# 07.net
KiCad netlist of a schematic drawn in Altium Designer
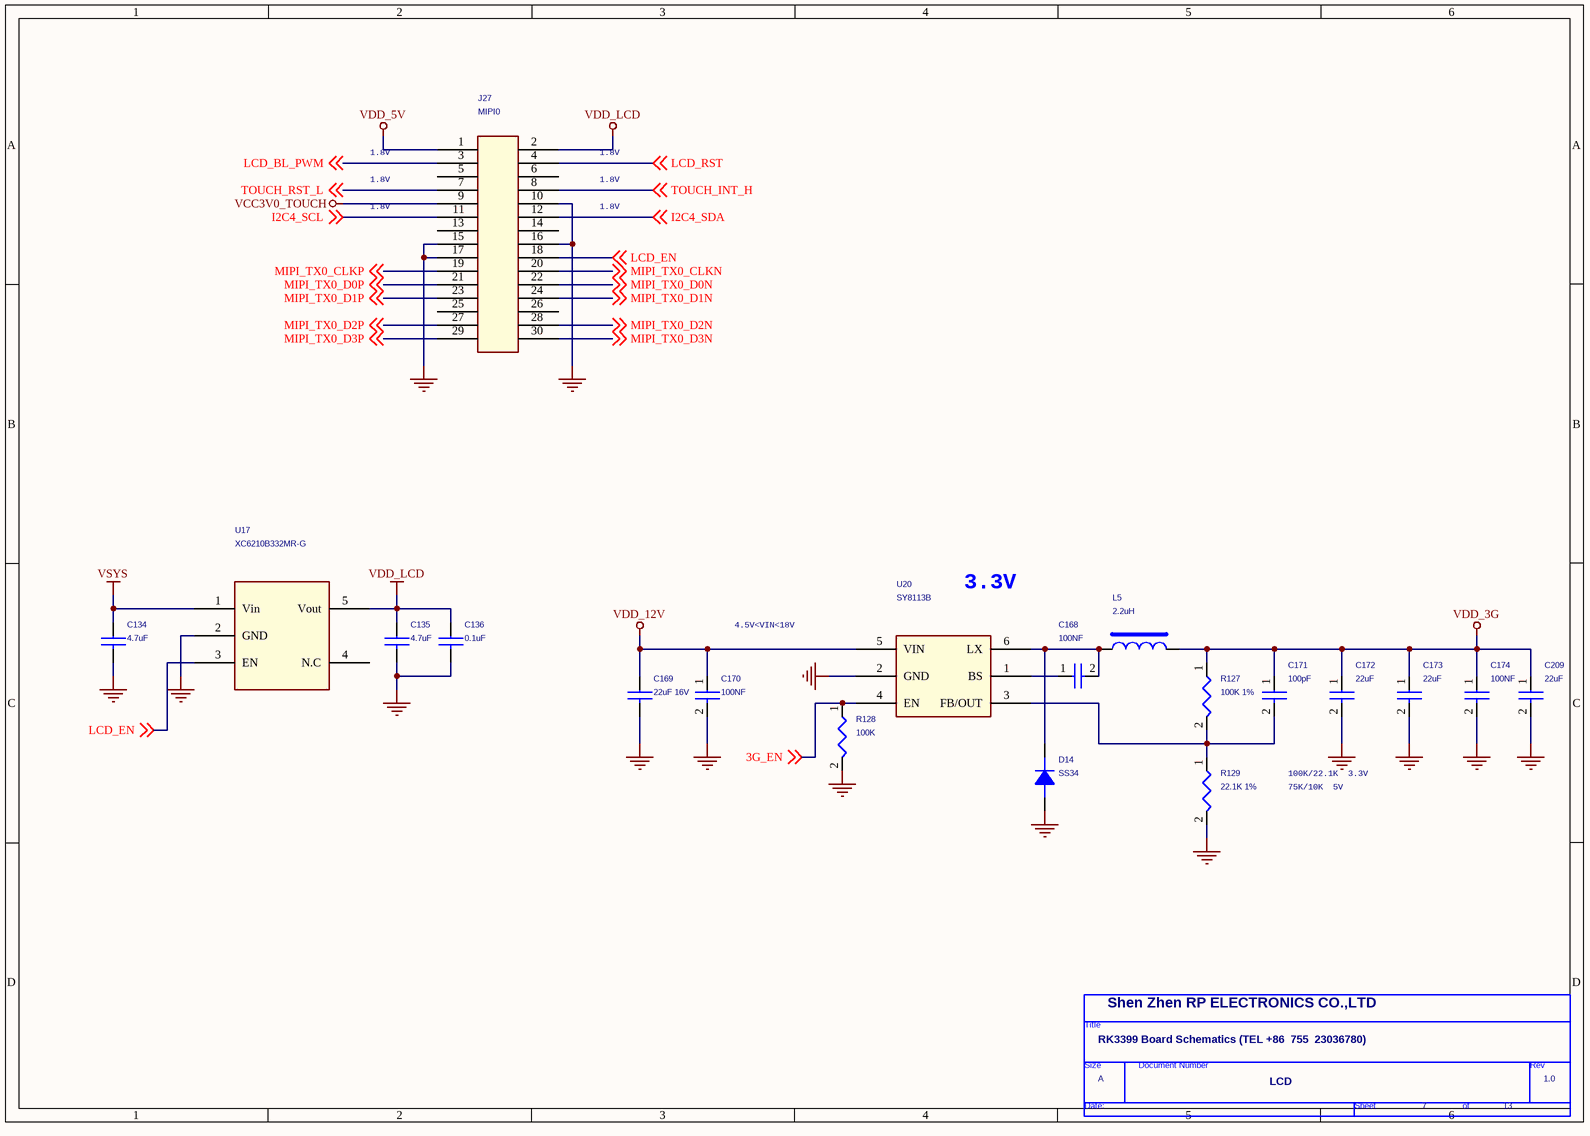
[diagram p0: 07.SchDoc]

(export (version "E")
  (design (tool "Eeschema 10.0.6"))
  (components
    (comp (ref "C134") (value "4.7uF") (libsource (lib "*") (part "CAP NP_Dup8")))
    (comp (ref "C135") (value "4.7uF") (libsource (lib "*") (part "CAP NP_Dup8")))
    (comp (ref "C136") (value "0.1uF") (libsource (lib "*") (part "CAP NP_Dup8")))
    (comp (ref "C168")
      (value "100NF")
      (description "cap,100.00nF,+/-10%,25V,X5R,C0402")
      (fields
        (field (name "VOLTAGE") "25V")
        (field (name "TOLERANCE") "10%")
        (field (name "CREATED BY") "JJJ")
      )
      (libsource (lib "*") (part "CAP NP_Dup2"))
    )
    (comp (ref "C169") (value "22uF 16V") (libsource (lib "*") (part "CAP NP_Dup8")))
    (comp (ref "C170")
      (value "100NF")
      (description "cap,100.00nF,+/-10%,25V,X5R,C0402")
      (fields
        (field (name "VOLTAGE") "25V")
        (field (name "MANUFACTURER") "TDK")
        (field (name "CREATED BY") "JJJ")
      )
      (libsource (lib "*") (part "CAP NP_Dup2"))
    )
    (comp (ref "C171")
      (value "100pF")
      (description "cap,100.00pF,+/-5%,50V,C0G,C0402")
      (fields
        (field (name "VOLTAGE") "50V")
        (field (name "MANUFACTURER") "TDK")
        (field (name "CREATED BY") "JJJ")
      )
      (libsource (lib "*") (part "CAP NP_Dup2"))
    )
    (comp (ref "C172")
      (value "22uF")
      (description "cap,22.00uF,+/-10%,10V,X5R,C0805")
      (fields
        (field (name "VOLTAGE") "10V")
        (field (name "MANUFACTURER") "TDK")
        (field (name "CREATED BY") "JJJ")
      )
      (libsource (lib "*") (part "CAP NP_Dup2"))
    )
    (comp (ref "C173")
      (value "22uF")
      (description "cap,10.00uF,+/-10%,10V,X5R,C0805")
      (fields
        (field (name "VOLTAGE") "10V")
        (field (name "MANUFACTURER") "TDK")
        (field (name "CREATED BY") "JJJ")
      )
      (libsource (lib "*") (part "CAP NP_Dup2"))
    )
    (comp (ref "C174")
      (value "100NF")
      (description "cap,100.00nF,+/-10%,16V,X5R,C0402")
      (fields
        (field (name "VOLTAGE") "16V")
        (field (name "MANUFACTURER") "TDK")
        (field (name "CREATED BY") "JJJ")
      )
      (libsource (lib "*") (part "CAP NP_Dup2"))
    )
    (comp (ref "C209")
      (value "22uF")
      (description "cap,22.00uF,+/-10%,10V,X5R,C0805")
      (fields
        (field (name "VOLTAGE") "10V")
        (field (name "MANUFACTURER") "TDK")
        (field (name "CREATED BY") "JJJ")
      )
      (libsource (lib "*") (part "CAP NP_Dup2"))
    )
    (comp (ref "D14") (value "SS34") (libsource (lib "*") (part "DIODE_Dup1")))
    (comp (ref "J27") (value "MIPI0") (libsource (lib "*") (part "CON20_5")))
    (comp (ref "L5")
      (value "2.2uH")
      (description "Power Inductor,3.3uH,0.2,IND_404030")
      (fields
        (field (name "MANUFACTURER") "sunlord")
        (field (name "TOLERANCE") "20%")
        (field (name "CREATED BY") "YTL")
      )
      (libsource (lib "*") (part "INDUCTORS OF FERRITE"))
    )
    (comp (ref "R127")
      (value "100K 1%")
      (footprint "0805")
      (description "通用厚膜电阻,75K,+/-1%,R0402,1/16W.")
      (fields
        (field (name "TOLERANCE") "1%")
        (field (name "MANUFACTURER") "YAGEO")
        (field (name "CREATED BY") "YTL")
      )
      (libsource (lib "*") (part "RESISTOR_Dup1"))
    )
    (comp (ref "R128")
      (value "100K")
      (footprint "0805")
      (description "通用厚膜电阻,10K,+/-1%,R0402,1/16W.")
      (fields
        (field (name "TOLERANCE") "1%")
        (field (name "MANUFACTURER") "YAGEO")
        (field (name "CREATED BY") "YTL")
      )
      (libsource (lib "*") (part "RESISTOR_Dup1"))
    )
    (comp (ref "R129")
      (value "22.1K 1%")
      (footprint "0805")
      (description "通用厚膜电阻,10K,+/-1%,R0402,1/16W.")
      (fields
        (field (name "TOLERANCE") "1%")
        (field (name "MANUFACTURER") "YAGEO")
        (field (name "CREATED BY") "YTL")
      )
      (libsource (lib "*") (part "RESISTOR_Dup1"))
    )
    (comp (ref "U17") (value "XC6210B332MR-G") (libsource (lib "*") (part "XC6219_2")))
    (comp (ref "U20")
      (value "SY8113B")
      (fields (field (name "MANUFACTURER") "Silergy（矽力杰）") (field (name "CREATED BY") "JJJ"))
      (libsource (lib "*") (part "DCDC_SY8113"))
    )
  )
  (nets
    (net (code "1") (name "3G_EN") (class "Default")
      (node (ref "R128") (pin "1") (pinfunction "1_1") (pintype "passive"))
      (node (ref "U20") (pin "4") (pinfunction "EN_4") (pintype "passive"))
    )
    (net (code "2") (name "GND") (class "Default")
      (node (ref "C134") (pin "2") (pinfunction "2_2") (pintype "passive"))
      (node (ref "C135") (pin "2") (pinfunction "2_2") (pintype "passive"))
      (node (ref "C136") (pin "2") (pinfunction "2_2") (pintype "passive"))
      (node (ref "C169") (pin "2") (pinfunction "2_2") (pintype "passive"))
      (node (ref "C170") (pin "2") (pinfunction "2_2") (pintype "passive"))
      (node (ref "C172") (pin "2") (pinfunction "2_2") (pintype "passive"))
      (node (ref "C173") (pin "2") (pinfunction "2_2") (pintype "passive"))
      (node (ref "C174") (pin "2") (pinfunction "2_2") (pintype "passive"))
      (node (ref "C209") (pin "2") (pinfunction "2_2") (pintype "passive"))
      (node (ref "D14") (pin "1") (pinfunction "A_1") (pintype "passive"))
      (node (ref "J27") (pin "10") (pinfunction "10_10") (pintype "passive"))
      (node (ref "J27") (pin "15") (pinfunction "15_15") (pintype "passive"))
      (node (ref "J27") (pin "16") (pinfunction "16_16") (pintype "passive"))
      (node (ref "J27") (pin "17") (pinfunction "17_17") (pintype "passive"))
      (node (ref "R128") (pin "2") (pinfunction "2_2") (pintype "passive"))
      (node (ref "R129") (pin "2") (pinfunction "2_2") (pintype "passive"))
      (node (ref "U17") (pin "2") (pinfunction "GND_2") (pintype "passive"))
      (node (ref "U20") (pin "2") (pinfunction "GND_2") (pintype "passive"))
    )
    (net (code "3") (name "I2C4_SCL") (class "Default")
      (node (ref "J27") (pin "11") (pinfunction "11_11") (pintype "passive"))
    )
    (net (code "4") (name "I2C4_SDA") (class "Default")
      (node (ref "J27") (pin "12") (pinfunction "12_12") (pintype "passive"))
    )
    (net (code "5") (name "LCD_BL_PWM") (class "Default")
      (node (ref "J27") (pin "3") (pinfunction "3_3") (pintype "passive"))
    )
    (net (code "6") (name "LCD_EN") (class "Default")
      (node (ref "J27") (pin "18") (pinfunction "18_18") (pintype "passive"))
      (node (ref "U17") (pin "3") (pinfunction "EN_3") (pintype "passive"))
    )
    (net (code "7") (name "LCD_RST") (class "Default")
      (node (ref "J27") (pin "4") (pinfunction "4_4") (pintype "passive"))
    )
    (net (code "8") (name "MIPI_TX0_CLKN") (class "Default")
      (node (ref "J27") (pin "20") (pinfunction "20_20") (pintype "passive"))
    )
    (net (code "9") (name "MIPI_TX0_CLKP") (class "Default")
      (node (ref "J27") (pin "19") (pinfunction "19_19") (pintype "passive"))
    )
    (net (code "10") (name "MIPI_TX0_D0N") (class "Default")
      (node (ref "J27") (pin "22") (pinfunction "22_22") (pintype "passive"))
    )
    (net (code "11") (name "MIPI_TX0_D0P") (class "Default")
      (node (ref "J27") (pin "21") (pinfunction "21_21") (pintype "passive"))
    )
    (net (code "12") (name "MIPI_TX0_D1N") (class "Default")
      (node (ref "J27") (pin "24") (pinfunction "24_24") (pintype "passive"))
    )
    (net (code "13") (name "MIPI_TX0_D1P") (class "Default")
      (node (ref "J27") (pin "23") (pinfunction "23_23") (pintype "passive"))
    )
    (net (code "14") (name "MIPI_TX0_D2N") (class "Default")
      (node (ref "J27") (pin "28") (pinfunction "28_28") (pintype "passive"))
    )
    (net (code "15") (name "MIPI_TX0_D2P") (class "Default")
      (node (ref "J27") (pin "27") (pinfunction "27_27") (pintype "passive"))
    )
    (net (code "16") (name "MIPI_TX0_D3N") (class "Default")
      (node (ref "J27") (pin "30") (pinfunction "30_30") (pintype "passive"))
    )
    (net (code "17") (name "MIPI_TX0_D3P") (class "Default")
      (node (ref "J27") (pin "29") (pinfunction "29_29") (pintype "passive"))
    )
    (net (code "18") (name "Net-(D14-K)") (class "Default")
      (node (ref "C168") (pin "2") (pinfunction "2_2") (pintype "passive"))
      (node (ref "D14") (pin "2") (pinfunction "K_2") (pintype "passive"))
      (node (ref "L5") (pin "1") (pinfunction "1_1") (pintype "passive"))
      (node (ref "U20") (pin "6") (pinfunction "LX_6") (pintype "passive"))
    )
    (net (code "19") (name "Net-(U20-BS)") (class "Default")
      (node (ref "C168") (pin "1") (pinfunction "1_1") (pintype "passive"))
      (node (ref "U20") (pin "1") (pinfunction "BS_1") (pintype "passive"))
    )
    (net (code "20") (name "Net-(U20-FB{slash}OUT)") (class "Default")
      (node (ref "C171") (pin "2") (pinfunction "2_2") (pintype "passive"))
      (node (ref "R127") (pin "2") (pinfunction "2_2") (pintype "passive"))
      (node (ref "R129") (pin "1") (pinfunction "1_1") (pintype "passive"))
      (node (ref "U20") (pin "3") (pinfunction "FB/OUT_3") (pintype "passive"))
    )
    (net (code "21") (name "TOUCH_INT_H") (class "Default")
      (node (ref "J27") (pin "8") (pinfunction "8_8") (pintype "passive"))
    )
    (net (code "22") (name "TOUCH_RST_L") (class "Default")
      (node (ref "J27") (pin "7") (pinfunction "7_7") (pintype "passive"))
    )
    (net (code "23") (name "VCC3V0_TOUCH") (class "Default")
      (node (ref "J27") (pin "9") (pinfunction "9_9") (pintype "passive"))
    )
    (net (code "24") (name "VDD_3G") (class "Default")
      (node (ref "C171") (pin "1") (pinfunction "1_1") (pintype "passive"))
      (node (ref "C172") (pin "1") (pinfunction "1_1") (pintype "passive"))
      (node (ref "C173") (pin "1") (pinfunction "1_1") (pintype "passive"))
      (node (ref "C174") (pin "1") (pinfunction "1_1") (pintype "passive"))
      (node (ref "C209") (pin "1") (pinfunction "1_1") (pintype "passive"))
      (node (ref "L5") (pin "2") (pinfunction "2_2") (pintype "passive"))
      (node (ref "R127") (pin "1") (pinfunction "1_1") (pintype "passive"))
    )
    (net (code "25") (name "VDD_5V") (class "Default")
      (node (ref "J27") (pin "1") (pinfunction "1_1") (pintype "passive"))
    )
    (net (code "26") (name "VDD_12V") (class "Default")
      (node (ref "C169") (pin "1") (pinfunction "1_1") (pintype "passive"))
      (node (ref "C170") (pin "1") (pinfunction "1_1") (pintype "passive"))
      (node (ref "U20") (pin "5") (pinfunction "VIN_5") (pintype "passive"))
    )
    (net (code "27") (name "VDD_LCD") (class "Default")
      (node (ref "C135") (pin "1") (pinfunction "1_1") (pintype "passive"))
      (node (ref "C136") (pin "1") (pinfunction "1_1") (pintype "passive"))
      (node (ref "J27") (pin "2") (pinfunction "2_2") (pintype "passive"))
      (node (ref "U17") (pin "5") (pinfunction "Vout_5") (pintype "passive"))
    )
    (net (code "28") (name "VSYS") (class "Default")
      (node (ref "C134") (pin "1") (pinfunction "1_1") (pintype "passive"))
      (node (ref "U17") (pin "1") (pinfunction "Vin_1") (pintype "passive"))
    )
    (net (code "29") (name "unconnected-(J27-Pad5)") (class "Default")
      (node (ref "J27") (pin "5") (pinfunction "5_5") (pintype "passive"))
    )
    (net (code "30") (name "unconnected-(J27-Pad6)") (class "Default")
      (node (ref "J27") (pin "6") (pinfunction "6_6") (pintype "passive"))
    )
    (net (code "31") (name "unconnected-(J27-Pad13)") (class "Default")
      (node (ref "J27") (pin "13") (pinfunction "13_13") (pintype "passive"))
    )
    (net (code "32") (name "unconnected-(J27-Pad14)") (class "Default")
      (node (ref "J27") (pin "14") (pinfunction "14_14") (pintype "passive"))
    )
    (net (code "33") (name "unconnected-(J27-Pad25)") (class "Default")
      (node (ref "J27") (pin "25") (pinfunction "25_25") (pintype "passive"))
    )
    (net (code "34") (name "unconnected-(J27-Pad26)") (class "Default")
      (node (ref "J27") (pin "26") (pinfunction "26_26") (pintype "passive"))
    )
    (net (code "35") (name "unconnected-(U17-N.C-Pad4)") (class "Default")
      (node (ref "U17") (pin "4") (pinfunction "N.C_4") (pintype "passive"))
    )
  )
)
